# twip-pb2.net
KiCad netlist of a schematic drawn in EAGLE
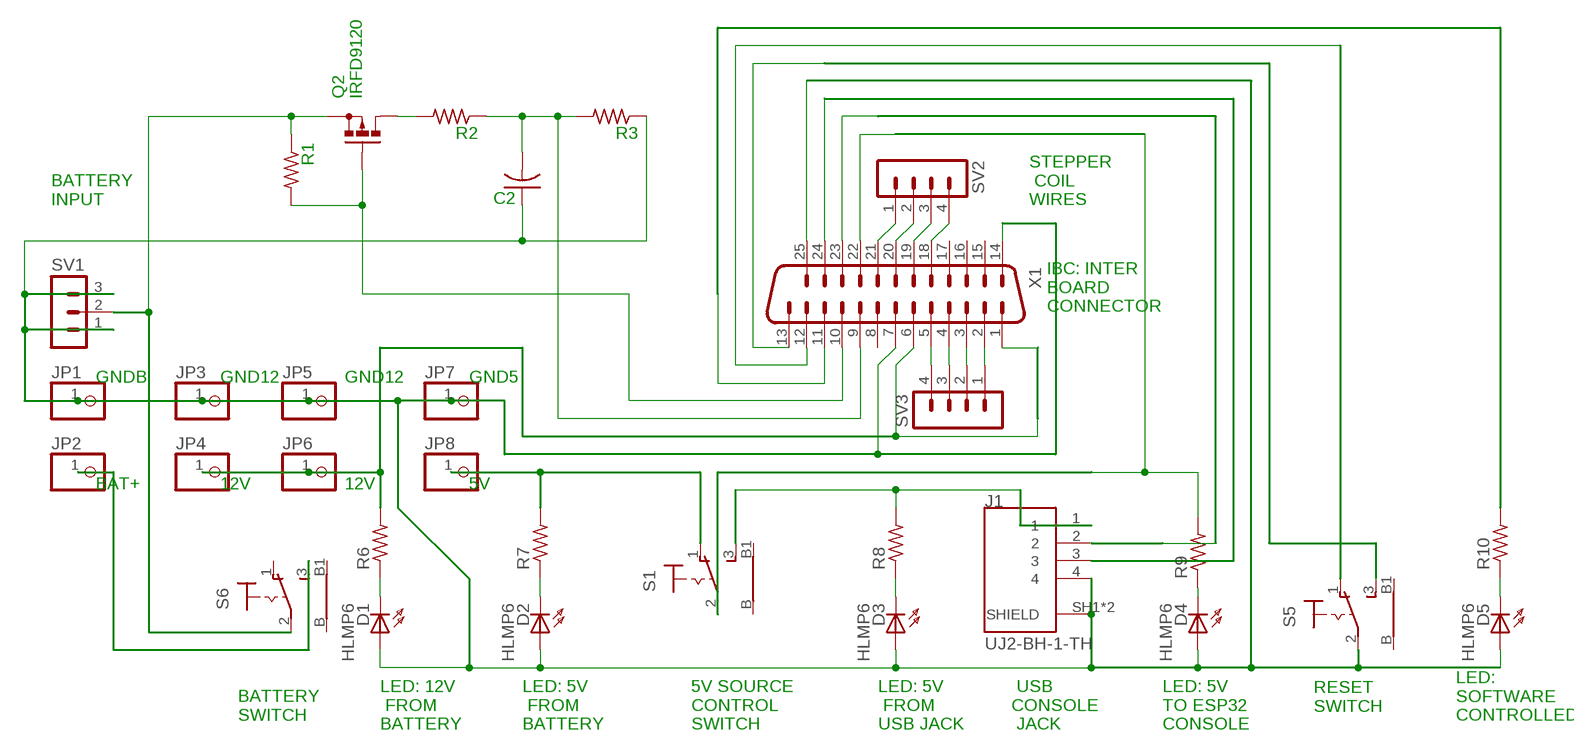
[diagram p0: schematic, sheet 1]

(export (version "E")
  (design (tool "Eeschema 10.0.6"))
  (components
    (comp (ref "C2")
      (value "C-US050-025X075")
      (footprint "eagle-import:C050-025X075")
      (libsource (lib "eagle-import") (part "C-US050-025X075"))
    )
    (comp (ref "D1")
      (value "HLMP6")
      (footprint "eagle-import:HLMP6")
      (fields (field (name "MF") "AGILENT TECHNOLOGIES") (field (name "MPN") "HLMP-6500"))
      (libsource (lib "eagle-import") (part "HLMP6"))
    )
    (comp (ref "D2")
      (value "HLMP6")
      (footprint "eagle-import:HLMP6")
      (fields (field (name "MF") "AGILENT TECHNOLOGIES") (field (name "MPN") "HLMP-6500"))
      (libsource (lib "eagle-import") (part "HLMP6"))
    )
    (comp (ref "D3")
      (value "HLMP6")
      (footprint "eagle-import:HLMP6")
      (fields (field (name "MF") "AGILENT TECHNOLOGIES") (field (name "MPN") "HLMP-6500"))
      (libsource (lib "eagle-import") (part "HLMP6"))
    )
    (comp (ref "D4")
      (value "HLMP6")
      (footprint "eagle-import:HLMP6")
      (fields (field (name "MF") "AGILENT TECHNOLOGIES") (field (name "MPN") "HLMP-6500"))
      (libsource (lib "eagle-import") (part "HLMP6"))
    )
    (comp (ref "D5")
      (value "HLMP6")
      (footprint "eagle-import:HLMP6")
      (fields (field (name "MF") "AGILENT TECHNOLOGIES") (field (name "MPN") "HLMP-6500"))
      (libsource (lib "eagle-import") (part "HLMP6"))
    )
    (comp (ref "J1")
      (value "UJ2-BH-1-TH")
      (footprint "eagle-import:CUI_UJ2-BH-1-TH")
      (fields (field (name "MANUFACTURER") "CUI INC"))
      (libsource (lib "eagle-import") (part "UJ2-BH-1-TH"))
    )
    (comp (ref "JP1")
      (value "PINHD-1X1")
      (footprint "eagle-import:1X01")
      (libsource (lib "eagle-import") (part "PINHD-1X1"))
    )
    (comp (ref "JP2")
      (value "PINHD-1X1")
      (footprint "eagle-import:1X01")
      (libsource (lib "eagle-import") (part "PINHD-1X1"))
    )
    (comp (ref "JP3")
      (value "PINHD-1X1")
      (footprint "eagle-import:1X01")
      (libsource (lib "eagle-import") (part "PINHD-1X1"))
    )
    (comp (ref "JP4")
      (value "PINHD-1X1")
      (footprint "eagle-import:1X01")
      (libsource (lib "eagle-import") (part "PINHD-1X1"))
    )
    (comp (ref "JP5")
      (value "PINHD-1X1")
      (footprint "eagle-import:1X01")
      (libsource (lib "eagle-import") (part "PINHD-1X1"))
    )
    (comp (ref "JP6")
      (value "PINHD-1X1")
      (footprint "eagle-import:1X01")
      (libsource (lib "eagle-import") (part "PINHD-1X1"))
    )
    (comp (ref "JP7")
      (value "PINHD-1X1")
      (footprint "eagle-import:1X01")
      (libsource (lib "eagle-import") (part "PINHD-1X1"))
    )
    (comp (ref "JP8")
      (value "PINHD-1X1")
      (footprint "eagle-import:1X01")
      (libsource (lib "eagle-import") (part "PINHD-1X1"))
    )
    (comp (ref "Q2")
      (value "IRFD9120")
      (footprint "eagle-import:C370-01")
      (libsource (lib "eagle-import") (part "IRFD9120"))
    )
    (comp (ref "R1")
      (value "R-US_0207/10")
      (footprint "eagle-import:0207_10")
      (libsource (lib "eagle-import") (part "R-US_0207/10"))
    )
    (comp (ref "R2")
      (value "R-US_0207/10")
      (footprint "eagle-import:0207_10")
      (libsource (lib "eagle-import") (part "R-US_0207/10"))
    )
    (comp (ref "R3")
      (value "R-US_0207/10")
      (footprint "eagle-import:0207_10")
      (libsource (lib "eagle-import") (part "R-US_0207/10"))
    )
    (comp (ref "R6")
      (value "R-US_0207/10")
      (footprint "eagle-import:0207_10")
      (libsource (lib "eagle-import") (part "R-US_0207/10"))
    )
    (comp (ref "R7")
      (value "R-US_0207/10")
      (footprint "eagle-import:0207_10")
      (libsource (lib "eagle-import") (part "R-US_0207/10"))
    )
    (comp (ref "R8")
      (value "R-US_0207/10")
      (footprint "eagle-import:0207_10")
      (libsource (lib "eagle-import") (part "R-US_0207/10"))
    )
    (comp (ref "R9")
      (value "R-US_0207/10")
      (footprint "eagle-import:0207_10")
      (libsource (lib "eagle-import") (part "R-US_0207/10"))
    )
    (comp (ref "R10")
      (value "R-US_0207/10")
      (footprint "eagle-import:0207_10")
      (libsource (lib "eagle-import") (part "R-US_0207/10"))
    )
    (comp (ref "S1")
      (value "9070-1W")
      (footprint "eagle-import:9070-1W")
      (libsource (lib "eagle-import") (part "9070-1W"))
    )
    (comp (ref "S5")
      (value "9070-1W")
      (footprint "eagle-import:9070-1W")
      (libsource (lib "eagle-import") (part "9070-1W"))
    )
    (comp (ref "S6")
      (value "9070-1W")
      (footprint "eagle-import:9070-1W")
      (libsource (lib "eagle-import") (part "9070-1W"))
    )
    (comp (ref "SV1")
      (value "MA03-1")
      (footprint "eagle-import:MA03-1")
      (libsource (lib "eagle-import") (part "MA03-1"))
    )
    (comp (ref "SV2")
      (value "MA04-1")
      (footprint "eagle-import:MA04-1")
      (libsource (lib "eagle-import") (part "MA04-1"))
    )
    (comp (ref "SV3")
      (value "MA04-1")
      (footprint "eagle-import:MA04-1")
      (libsource (lib "eagle-import") (part "MA04-1"))
    )
    (comp (ref "X1")
      (value "M25VP")
      (footprint "eagle-import:M25VP")
      (libsource (lib "eagle-import") (part "M25VP"))
    )
  )
  (nets
    (net (code "1") (name "Net-(C2-Pad2)") (class "Default")
      (node (ref "C2") (pin "2") (pinfunction "2_2") (pintype "passive"))
      (node (ref "R2") (pin "1") (pinfunction "1_1") (pintype "passive"))
      (node (ref "R3") (pin "2") (pinfunction "2_2") (pintype "passive"))
      (node (ref "X1") (pin "9") (pinfunction "9_9") (pintype "passive"))
    )
    (net (code "2") (name "Net-(D1-PadK)") (class "Default")
      (node (ref "D1") (pin "K") (pinfunction "K_K") (pintype "passive"))
      (node (ref "R6") (pin "1") (pinfunction "1_1") (pintype "passive"))
    )
    (net (code "3") (name "Net-(D2-PadK)") (class "Default")
      (node (ref "D2") (pin "K") (pinfunction "K_K") (pintype "passive"))
      (node (ref "R7") (pin "1") (pinfunction "1_1") (pintype "passive"))
    )
    (net (code "4") (name "Net-(D3-PadK)") (class "Default")
      (node (ref "D3") (pin "K") (pinfunction "K_K") (pintype "passive"))
      (node (ref "R8") (pin "1") (pinfunction "1_1") (pintype "passive"))
    )
    (net (code "5") (name "Net-(D4-PadK)") (class "Default")
      (node (ref "D4") (pin "K") (pinfunction "K_K") (pintype "passive"))
      (node (ref "R9") (pin "1") (pinfunction "1_1") (pintype "passive"))
    )
    (net (code "6") (name "Net-(D5-PadK)") (class "Default")
      (node (ref "D5") (pin "K") (pinfunction "K_K") (pintype "passive"))
      (node (ref "R10") (pin "1") (pinfunction "1_1") (pintype "passive"))
    )
    (net (code "7") (name "Net-(J1-Pad2)") (class "Default")
      (node (ref "J1") (pin "2") (pinfunction "2_2") (pintype "passive"))
      (node (ref "X1") (pin "23") (pinfunction "23_23") (pintype "passive"))
    )
    (net (code "8") (name "Net-(J1-Pad3)") (class "Default")
      (node (ref "J1") (pin "3") (pinfunction "3_3") (pintype "passive"))
      (node (ref "X1") (pin "24") (pinfunction "24_24") (pintype "passive"))
    )
    (net (code "9") (name "Net-(JP4-Pad1)") (class "Default")
      (node (ref "JP4") (pin "1") (pinfunction "1_1") (pintype "passive"))
      (node (ref "JP6") (pin "1") (pinfunction "1_1") (pintype "passive"))
      (node (ref "R6") (pin "2") (pinfunction "2_2") (pintype "passive"))
      (node (ref "X1") (pin "1") (pinfunction "1_1") (pintype "passive"))
      (node (ref "X1") (pin "6") (pinfunction "6_6") (pintype "passive"))
    )
    (net (code "10") (name "Net-(Q2-D-PadD1)") (class "Default")
      (node (ref "Q2") (pin "D") (pinfunction "D_D") (pintype "passive"))
      (node (ref "Q2") (pin "D1") (pinfunction "D_D1") (pintype "passive"))
      (node (ref "R2") (pin "2") (pinfunction "2_2") (pintype "passive"))
    )
    (net (code "11") (name "Net-(Q2-PadG)") (class "Default")
      (node (ref "Q2") (pin "G") (pinfunction "G_G") (pintype "passive"))
      (node (ref "R1") (pin "2") (pinfunction "2_2") (pintype "passive"))
      (node (ref "X1") (pin "10") (pinfunction "10_10") (pintype "passive"))
    )
    (net (code "12") (name "Net-(R10-Pad2)") (class "Default")
      (node (ref "R10") (pin "2") (pinfunction "2_2") (pintype "passive"))
      (node (ref "X1") (pin "11") (pinfunction "11_11") (pintype "passive"))
    )
    (net (code "13") (name "Net-(S1-O)") (class "Default")
      (node (ref "JP8") (pin "1") (pinfunction "1_1") (pintype "passive"))
      (node (ref "R7") (pin "2") (pinfunction "2_2") (pintype "passive"))
      (node (ref "S1") (pin "1") (pinfunction "O_1") (pintype "passive"))
    )
    (net (code "14") (name "Net-(S1-P)") (class "Default")
      (node (ref "R9") (pin "2") (pinfunction "2_2") (pintype "passive"))
      (node (ref "S1") (pin "2") (pinfunction "P_2") (pintype "passive"))
      (node (ref "X1") (pin "22") (pinfunction "22_22") (pintype "passive"))
    )
    (net (code "15") (name "Net-(S1-S)") (class "Default")
      (node (ref "J1") (pin "1") (pinfunction "1_1") (pintype "passive"))
      (node (ref "R8") (pin "2") (pinfunction "2_2") (pintype "passive"))
      (node (ref "S1") (pin "3") (pinfunction "S_3") (pintype "passive"))
    )
    (net (code "16") (name "Net-(S5-O)") (class "Default")
      (node (ref "S5") (pin "1") (pinfunction "O_1") (pintype "passive"))
      (node (ref "X1") (pin "12") (pinfunction "12_12") (pintype "passive"))
    )
    (net (code "17") (name "Net-(S5-P)") (class "Default")
      (node (ref "C2") (pin "1") (pinfunction "1_1") (pintype "passive"))
      (node (ref "D1") (pin "A") (pinfunction "A_A") (pintype "passive"))
      (node (ref "D2") (pin "A") (pinfunction "A_A") (pintype "passive"))
      (node (ref "D3") (pin "A") (pinfunction "A_A") (pintype "passive"))
      (node (ref "D4") (pin "A") (pinfunction "A_A") (pintype "passive"))
      (node (ref "D5") (pin "A") (pinfunction "A_A") (pintype "passive"))
      (node (ref "J1") (pin "4") (pinfunction "4_4") (pintype "passive"))
      (node (ref "J1") (pin "SH1") (pinfunction "SHIELD_SH1") (pintype "passive"))
      (node (ref "J1") (pin "SH2") (pinfunction "SHIELD_SH2") (pintype "passive"))
      (node (ref "JP1") (pin "1") (pinfunction "1_1") (pintype "passive"))
      (node (ref "JP3") (pin "1") (pinfunction "1_1") (pintype "passive"))
      (node (ref "JP5") (pin "1") (pinfunction "1_1") (pintype "passive"))
      (node (ref "JP7") (pin "1") (pinfunction "1_1") (pintype "passive"))
      (node (ref "R3") (pin "1") (pinfunction "1_1") (pintype "passive"))
      (node (ref "S5") (pin "2") (pinfunction "P_2") (pintype "passive"))
      (node (ref "SV1") (pin "1") (pinfunction "1_1") (pintype "passive"))
      (node (ref "SV1") (pin "3") (pinfunction "3_3") (pintype "passive"))
      (node (ref "X1") (pin "14") (pinfunction "14_14") (pintype "passive"))
      (node (ref "X1") (pin "25") (pinfunction "25_25") (pintype "passive"))
      (node (ref "X1") (pin "7") (pinfunction "7_7") (pintype "passive"))
    )
    (net (code "18") (name "Net-(S5-S)") (class "Default")
      (node (ref "S5") (pin "3") (pinfunction "S_3") (pintype "passive"))
      (node (ref "X1") (pin "13") (pinfunction "13_13") (pintype "passive"))
    )
    (net (code "19") (name "Net-(S6-P)") (class "Default")
      (node (ref "Q2") (pin "S") (pinfunction "S_S") (pintype "passive"))
      (node (ref "R1") (pin "1") (pinfunction "1_1") (pintype "passive"))
      (node (ref "S6") (pin "2") (pinfunction "P_2") (pintype "passive"))
      (node (ref "SV1") (pin "2") (pinfunction "2_2") (pintype "passive"))
    )
    (net (code "20") (name "Net-(S6-S)") (class "Default")
      (node (ref "JP2") (pin "1") (pinfunction "1_1") (pintype "passive"))
      (node (ref "S6") (pin "3") (pinfunction "S_3") (pintype "passive"))
    )
    (net (code "21") (name "Net-(SV2-Pad1)") (class "Default")
      (node (ref "SV2") (pin "1") (pinfunction "1_1") (pintype "passive"))
      (node (ref "X1") (pin "21") (pinfunction "21_21") (pintype "passive"))
    )
    (net (code "22") (name "Net-(SV2-Pad2)") (class "Default")
      (node (ref "SV2") (pin "2") (pinfunction "2_2") (pintype "passive"))
      (node (ref "X1") (pin "20") (pinfunction "20_20") (pintype "passive"))
    )
    (net (code "23") (name "Net-(SV2-Pad3)") (class "Default")
      (node (ref "SV2") (pin "3") (pinfunction "3_3") (pintype "passive"))
      (node (ref "X1") (pin "19") (pinfunction "19_19") (pintype "passive"))
    )
    (net (code "24") (name "Net-(SV2-Pad4)") (class "Default")
      (node (ref "SV2") (pin "4") (pinfunction "4_4") (pintype "passive"))
      (node (ref "X1") (pin "18") (pinfunction "18_18") (pintype "passive"))
    )
    (net (code "25") (name "Net-(SV3-Pad1)") (class "Default")
      (node (ref "SV3") (pin "1") (pinfunction "1_1") (pintype "passive"))
      (node (ref "X1") (pin "2") (pinfunction "2_2") (pintype "passive"))
    )
    (net (code "26") (name "Net-(SV3-Pad2)") (class "Default")
      (node (ref "SV3") (pin "2") (pinfunction "2_2") (pintype "passive"))
      (node (ref "X1") (pin "3") (pinfunction "3_3") (pintype "passive"))
    )
    (net (code "27") (name "Net-(SV3-Pad3)") (class "Default")
      (node (ref "SV3") (pin "3") (pinfunction "3_3") (pintype "passive"))
      (node (ref "X1") (pin "4") (pinfunction "4_4") (pintype "passive"))
    )
    (net (code "28") (name "Net-(SV3-Pad4)") (class "Default")
      (node (ref "SV3") (pin "4") (pinfunction "4_4") (pintype "passive"))
      (node (ref "X1") (pin "5") (pinfunction "5_5") (pintype "passive"))
    )
    (net (code "29") (name "unconnected-(S1-PadB)") (class "Default")
      (node (ref "S1") (pin "B") (pinfunction "B_B") (pintype "passive"))
    )
    (net (code "30") (name "unconnected-(S1-PadB1)") (class "Default")
      (node (ref "S1") (pin "B1") (pinfunction "B1_B1") (pintype "passive"))
    )
    (net (code "31") (name "unconnected-(S5-PadB)") (class "Default")
      (node (ref "S5") (pin "B") (pinfunction "B_B") (pintype "passive"))
    )
    (net (code "32") (name "unconnected-(S5-PadB1)") (class "Default")
      (node (ref "S5") (pin "B1") (pinfunction "B1_B1") (pintype "passive"))
    )
    (net (code "33") (name "unconnected-(S6-O-Pad1)") (class "Default")
      (node (ref "S6") (pin "1") (pinfunction "O_1") (pintype "passive"))
    )
    (net (code "34") (name "unconnected-(S6-PadB)") (class "Default")
      (node (ref "S6") (pin "B") (pinfunction "B_B") (pintype "passive"))
    )
    (net (code "35") (name "unconnected-(S6-PadB1)") (class "Default")
      (node (ref "S6") (pin "B1") (pinfunction "B1_B1") (pintype "passive"))
    )
    (net (code "36") (name "unconnected-(X1-Pad8)") (class "Default")
      (node (ref "X1") (pin "8") (pinfunction "8_8") (pintype "passive"))
    )
    (net (code "37") (name "unconnected-(X1-Pad15)") (class "Default")
      (node (ref "X1") (pin "15") (pinfunction "15_15") (pintype "passive"))
    )
    (net (code "38") (name "unconnected-(X1-Pad16)") (class "Default")
      (node (ref "X1") (pin "16") (pinfunction "16_16") (pintype "passive"))
    )
    (net (code "39") (name "unconnected-(X1-Pad17)") (class "Default")
      (node (ref "X1") (pin "17") (pinfunction "17_17") (pintype "passive"))
    )
  )
)
